# 1LED_pullup.net
KiCad netlist of a schematic drawn in EAGLE
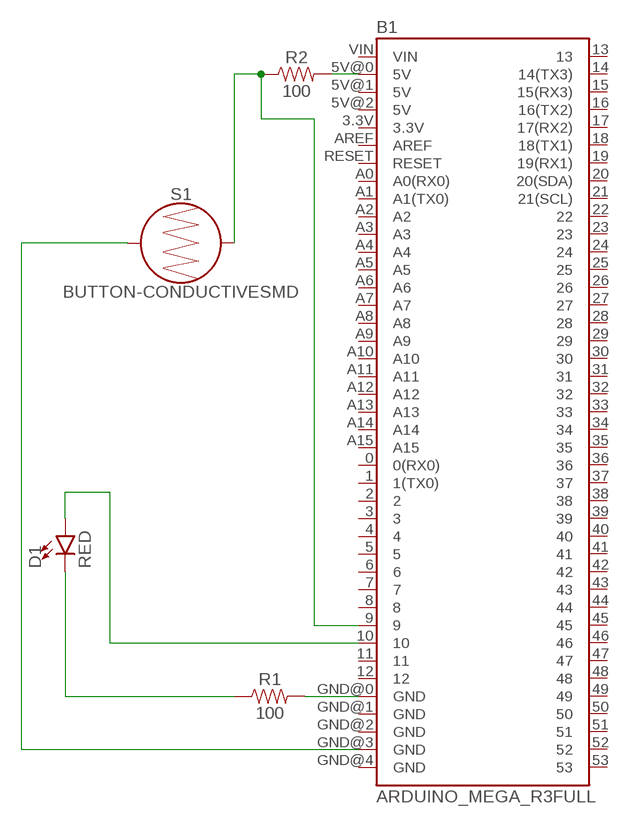
[diagram p0: schematic, sheet 1]

(export (version "E")
  (design (tool "Eeschema 10.0.6"))
  (components
    (comp (ref "B1")
      (value "ARDUINO_MEGA_R3FULL")
      (footprint "eagle-import:ARDUINO_MEGA")
      (libsource (lib "eagle-import") (part "ARDUINO_MEGA_R3FULL"))
    )
    (comp (ref "D1")
      (value "RED")
      (footprint "eagle-import:LED-0603")
      (libsource (lib "eagle-import") (part "LED-RED0603"))
    )
    (comp (ref "R1")
      (value "100")
      (footprint "eagle-import:0603")
      (libsource (lib "eagle-import") (part "100OHM-0603-1/4W-5%"))
    )
    (comp (ref "R2")
      (value "100")
      (footprint "eagle-import:0603")
      (libsource (lib "eagle-import") (part "100OHM-0603-1/4W-5%"))
    )
    (comp (ref "S1")
      (value "BUTTON-CONDUCTIVESMD")
      (footprint "eagle-import:BUTTON-CONDUCTIVE")
      (libsource (lib "eagle-import") (part "BUTTON-CONDUCTIVESMD"))
    )
  )
  (nets
    (net (code "1") (name "Net-(B1-5V-Pad5V@0)") (class "Default")
      (node (ref "B1") (pin "5V@0") (pinfunction "5V_5V@0") (pintype "bidirectional"))
      (node (ref "R2") (pin "2") (pinfunction "2_2") (pintype "passive"))
    )
    (net (code "2") (name "Net-(B1-GND-PadGND@0)") (class "Default")
      (node (ref "B1") (pin "GND@0") (pinfunction "GND_GND@0") (pintype "bidirectional"))
      (node (ref "R1") (pin "2") (pinfunction "2_2") (pintype "passive"))
    )
    (net (code "3") (name "Net-(B1-GND-PadGND@3)") (class "Default")
      (node (ref "B1") (pin "GND@3") (pinfunction "GND_GND@3") (pintype "bidirectional"))
      (node (ref "S1") (pin "1") (pinfunction "1_1") (pintype "passive"))
    )
    (net (code "4") (name "Net-(B1-Pad9)") (class "Default")
      (node (ref "B1") (pin "9") (pinfunction "9_9") (pintype "bidirectional"))
      (node (ref "R2") (pin "1") (pinfunction "1_1") (pintype "passive"))
      (node (ref "S1") (pin "2") (pinfunction "2_2") (pintype "passive"))
    )
    (net (code "5") (name "Net-(B1-Pad10)") (class "Default")
      (node (ref "B1") (pin "10") (pinfunction "10_10") (pintype "bidirectional"))
      (node (ref "D1") (pin "A") (pinfunction "A_A") (pintype "passive"))
    )
    (net (code "6") (name "Net-(D1-PadC)") (class "Default")
      (node (ref "D1") (pin "C") (pinfunction "C_C") (pintype "passive"))
      (node (ref "R1") (pin "1") (pinfunction "1_1") (pintype "passive"))
    )
    (net (code "7") (name "unconnected-(B1-0(RX0)-Pad0)") (class "Default")
      (node (ref "B1") (pin "0") (pinfunction "0(RX0)_0") (pintype "bidirectional"))
    )
    (net (code "8") (name "unconnected-(B1-1(TX0)-Pad1)") (class "Default")
      (node (ref "B1") (pin "1") (pinfunction "1(TX0)_1") (pintype "bidirectional"))
    )
    (net (code "9") (name "unconnected-(B1-5V-Pad5V@1)") (class "Default")
      (node (ref "B1") (pin "5V@1") (pinfunction "5V_5V@1") (pintype "bidirectional"))
    )
    (net (code "10") (name "unconnected-(B1-5V-Pad5V@2)") (class "Default")
      (node (ref "B1") (pin "5V@2") (pinfunction "5V_5V@2") (pintype "bidirectional"))
    )
    (net (code "11") (name "unconnected-(B1-14(TX3)-Pad14)") (class "Default")
      (node (ref "B1") (pin "14") (pinfunction "14(TX3)_14") (pintype "bidirectional"))
    )
    (net (code "12") (name "unconnected-(B1-15(RX3)-Pad15)") (class "Default")
      (node (ref "B1") (pin "15") (pinfunction "15(RX3)_15") (pintype "bidirectional"))
    )
    (net (code "13") (name "unconnected-(B1-16(TX2)-Pad16)") (class "Default")
      (node (ref "B1") (pin "16") (pinfunction "16(TX2)_16") (pintype "bidirectional"))
    )
    (net (code "14") (name "unconnected-(B1-17(RX2)-Pad17)") (class "Default")
      (node (ref "B1") (pin "17") (pinfunction "17(RX2)_17") (pintype "bidirectional"))
    )
    (net (code "15") (name "unconnected-(B1-18(TX1)-Pad18)") (class "Default")
      (node (ref "B1") (pin "18") (pinfunction "18(TX1)_18") (pintype "bidirectional"))
    )
    (net (code "16") (name "unconnected-(B1-19(RX1)-Pad19)") (class "Default")
      (node (ref "B1") (pin "19") (pinfunction "19(RX1)_19") (pintype "bidirectional"))
    )
    (net (code "17") (name "unconnected-(B1-20(SDA)-Pad20)") (class "Default")
      (node (ref "B1") (pin "20") (pinfunction "20(SDA)_20") (pintype "bidirectional"))
    )
    (net (code "18") (name "unconnected-(B1-21(SCL)-Pad21)") (class "Default")
      (node (ref "B1") (pin "21") (pinfunction "21(SCL)_21") (pintype "bidirectional"))
    )
    (net (code "19") (name "unconnected-(B1-A0(RX0)-PadA0)") (class "Default")
      (node (ref "B1") (pin "A0") (pinfunction "A0(RX0)_A0") (pintype "bidirectional"))
    )
    (net (code "20") (name "unconnected-(B1-A1(TX0)-PadA1)") (class "Default")
      (node (ref "B1") (pin "A1") (pinfunction "A1(TX0)_A1") (pintype "bidirectional"))
    )
    (net (code "21") (name "unconnected-(B1-GND-PadGND@1)") (class "Default")
      (node (ref "B1") (pin "GND@1") (pinfunction "GND_GND@1") (pintype "bidirectional"))
    )
    (net (code "22") (name "unconnected-(B1-GND-PadGND@2)") (class "Default")
      (node (ref "B1") (pin "GND@2") (pinfunction "GND_GND@2") (pintype "bidirectional"))
    )
    (net (code "23") (name "unconnected-(B1-GND-PadGND@4)") (class "Default")
      (node (ref "B1") (pin "GND@4") (pinfunction "GND_GND@4") (pintype "bidirectional"))
    )
    (net (code "24") (name "unconnected-(B1-Pad2)") (class "Default")
      (node (ref "B1") (pin "2") (pinfunction "2_2") (pintype "bidirectional"))
    )
    (net (code "25") (name "unconnected-(B1-Pad3)") (class "Default")
      (node (ref "B1") (pin "3") (pinfunction "3_3") (pintype "bidirectional"))
    )
    (net (code "26") (name "unconnected-(B1-Pad3.3V)") (class "Default")
      (node (ref "B1") (pin "3.3V") (pinfunction "3.3V_3.3V") (pintype "bidirectional"))
    )
    (net (code "27") (name "unconnected-(B1-Pad4)") (class "Default")
      (node (ref "B1") (pin "4") (pinfunction "4_4") (pintype "bidirectional"))
    )
    (net (code "28") (name "unconnected-(B1-Pad5)") (class "Default")
      (node (ref "B1") (pin "5") (pinfunction "5_5") (pintype "bidirectional"))
    )
    (net (code "29") (name "unconnected-(B1-Pad6)") (class "Default")
      (node (ref "B1") (pin "6") (pinfunction "6_6") (pintype "bidirectional"))
    )
    (net (code "30") (name "unconnected-(B1-Pad7)") (class "Default")
      (node (ref "B1") (pin "7") (pinfunction "7_7") (pintype "bidirectional"))
    )
    (net (code "31") (name "unconnected-(B1-Pad8)") (class "Default")
      (node (ref "B1") (pin "8") (pinfunction "8_8") (pintype "bidirectional"))
    )
    (net (code "32") (name "unconnected-(B1-Pad11)") (class "Default")
      (node (ref "B1") (pin "11") (pinfunction "11_11") (pintype "bidirectional"))
    )
    (net (code "33") (name "unconnected-(B1-Pad12)") (class "Default")
      (node (ref "B1") (pin "12") (pinfunction "12_12") (pintype "bidirectional"))
    )
    (net (code "34") (name "unconnected-(B1-Pad13)") (class "Default")
      (node (ref "B1") (pin "13") (pinfunction "13_13") (pintype "bidirectional"))
    )
    (net (code "35") (name "unconnected-(B1-Pad22)") (class "Default")
      (node (ref "B1") (pin "22") (pinfunction "22_22") (pintype "bidirectional"))
    )
    (net (code "36") (name "unconnected-(B1-Pad23)") (class "Default")
      (node (ref "B1") (pin "23") (pinfunction "23_23") (pintype "bidirectional"))
    )
    (net (code "37") (name "unconnected-(B1-Pad24)") (class "Default")
      (node (ref "B1") (pin "24") (pinfunction "24_24") (pintype "bidirectional"))
    )
    (net (code "38") (name "unconnected-(B1-Pad25)") (class "Default")
      (node (ref "B1") (pin "25") (pinfunction "25_25") (pintype "bidirectional"))
    )
    (net (code "39") (name "unconnected-(B1-Pad26)") (class "Default")
      (node (ref "B1") (pin "26") (pinfunction "26_26") (pintype "bidirectional"))
    )
    (net (code "40") (name "unconnected-(B1-Pad27)") (class "Default")
      (node (ref "B1") (pin "27") (pinfunction "27_27") (pintype "bidirectional"))
    )
    (net (code "41") (name "unconnected-(B1-Pad28)") (class "Default")
      (node (ref "B1") (pin "28") (pinfunction "28_28") (pintype "bidirectional"))
    )
    (net (code "42") (name "unconnected-(B1-Pad29)") (class "Default")
      (node (ref "B1") (pin "29") (pinfunction "29_29") (pintype "bidirectional"))
    )
    (net (code "43") (name "unconnected-(B1-Pad30)") (class "Default")
      (node (ref "B1") (pin "30") (pinfunction "30_30") (pintype "bidirectional"))
    )
    (net (code "44") (name "unconnected-(B1-Pad31)") (class "Default")
      (node (ref "B1") (pin "31") (pinfunction "31_31") (pintype "bidirectional"))
    )
    (net (code "45") (name "unconnected-(B1-Pad32)") (class "Default")
      (node (ref "B1") (pin "32") (pinfunction "32_32") (pintype "bidirectional"))
    )
    (net (code "46") (name "unconnected-(B1-Pad33)") (class "Default")
      (node (ref "B1") (pin "33") (pinfunction "33_33") (pintype "bidirectional"))
    )
    (net (code "47") (name "unconnected-(B1-Pad34)") (class "Default")
      (node (ref "B1") (pin "34") (pinfunction "34_34") (pintype "bidirectional"))
    )
    (net (code "48") (name "unconnected-(B1-Pad35)") (class "Default")
      (node (ref "B1") (pin "35") (pinfunction "35_35") (pintype "bidirectional"))
    )
    (net (code "49") (name "unconnected-(B1-Pad36)") (class "Default")
      (node (ref "B1") (pin "36") (pinfunction "36_36") (pintype "bidirectional"))
    )
    (net (code "50") (name "unconnected-(B1-Pad37)") (class "Default")
      (node (ref "B1") (pin "37") (pinfunction "37_37") (pintype "bidirectional"))
    )
    (net (code "51") (name "unconnected-(B1-Pad38)") (class "Default")
      (node (ref "B1") (pin "38") (pinfunction "38_38") (pintype "bidirectional"))
    )
    (net (code "52") (name "unconnected-(B1-Pad39)") (class "Default")
      (node (ref "B1") (pin "39") (pinfunction "39_39") (pintype "bidirectional"))
    )
    (net (code "53") (name "unconnected-(B1-Pad40)") (class "Default")
      (node (ref "B1") (pin "40") (pinfunction "40_40") (pintype "bidirectional"))
    )
    (net (code "54") (name "unconnected-(B1-Pad41)") (class "Default")
      (node (ref "B1") (pin "41") (pinfunction "41_41") (pintype "bidirectional"))
    )
    (net (code "55") (name "unconnected-(B1-Pad42)") (class "Default")
      (node (ref "B1") (pin "42") (pinfunction "42_42") (pintype "bidirectional"))
    )
    (net (code "56") (name "unconnected-(B1-Pad43)") (class "Default")
      (node (ref "B1") (pin "43") (pinfunction "43_43") (pintype "bidirectional"))
    )
    (net (code "57") (name "unconnected-(B1-Pad44)") (class "Default")
      (node (ref "B1") (pin "44") (pinfunction "44_44") (pintype "bidirectional"))
    )
    (net (code "58") (name "unconnected-(B1-Pad45)") (class "Default")
      (node (ref "B1") (pin "45") (pinfunction "45_45") (pintype "bidirectional"))
    )
    (net (code "59") (name "unconnected-(B1-Pad46)") (class "Default")
      (node (ref "B1") (pin "46") (pinfunction "46_46") (pintype "bidirectional"))
    )
    (net (code "60") (name "unconnected-(B1-Pad47)") (class "Default")
      (node (ref "B1") (pin "47") (pinfunction "47_47") (pintype "bidirectional"))
    )
    (net (code "61") (name "unconnected-(B1-Pad48)") (class "Default")
      (node (ref "B1") (pin "48") (pinfunction "48_48") (pintype "bidirectional"))
    )
    (net (code "62") (name "unconnected-(B1-Pad49)") (class "Default")
      (node (ref "B1") (pin "49") (pinfunction "49_49") (pintype "bidirectional"))
    )
    (net (code "63") (name "unconnected-(B1-Pad50)") (class "Default")
      (node (ref "B1") (pin "50") (pinfunction "50_50") (pintype "bidirectional"))
    )
    (net (code "64") (name "unconnected-(B1-Pad51)") (class "Default")
      (node (ref "B1") (pin "51") (pinfunction "51_51") (pintype "bidirectional"))
    )
    (net (code "65") (name "unconnected-(B1-Pad52)") (class "Default")
      (node (ref "B1") (pin "52") (pinfunction "52_52") (pintype "bidirectional"))
    )
    (net (code "66") (name "unconnected-(B1-Pad53)") (class "Default")
      (node (ref "B1") (pin "53") (pinfunction "53_53") (pintype "bidirectional"))
    )
    (net (code "67") (name "unconnected-(B1-PadA2)") (class "Default")
      (node (ref "B1") (pin "A2") (pinfunction "A2_A2") (pintype "bidirectional"))
    )
    (net (code "68") (name "unconnected-(B1-PadA3)") (class "Default")
      (node (ref "B1") (pin "A3") (pinfunction "A3_A3") (pintype "bidirectional"))
    )
    (net (code "69") (name "unconnected-(B1-PadA4)") (class "Default")
      (node (ref "B1") (pin "A4") (pinfunction "A4_A4") (pintype "bidirectional"))
    )
    (net (code "70") (name "unconnected-(B1-PadA5)") (class "Default")
      (node (ref "B1") (pin "A5") (pinfunction "A5_A5") (pintype "bidirectional"))
    )
    (net (code "71") (name "unconnected-(B1-PadA6)") (class "Default")
      (node (ref "B1") (pin "A6") (pinfunction "A6_A6") (pintype "bidirectional"))
    )
    (net (code "72") (name "unconnected-(B1-PadA7)") (class "Default")
      (node (ref "B1") (pin "A7") (pinfunction "A7_A7") (pintype "bidirectional"))
    )
    (net (code "73") (name "unconnected-(B1-PadA8)") (class "Default")
      (node (ref "B1") (pin "A8") (pinfunction "A8_A8") (pintype "bidirectional"))
    )
    (net (code "74") (name "unconnected-(B1-PadA9)") (class "Default")
      (node (ref "B1") (pin "A9") (pinfunction "A9_A9") (pintype "bidirectional"))
    )
    (net (code "75") (name "unconnected-(B1-PadA10)") (class "Default")
      (node (ref "B1") (pin "A10") (pinfunction "A10_A10") (pintype "bidirectional"))
    )
    (net (code "76") (name "unconnected-(B1-PadA11)") (class "Default")
      (node (ref "B1") (pin "A11") (pinfunction "A11_A11") (pintype "bidirectional"))
    )
    (net (code "77") (name "unconnected-(B1-PadA12)") (class "Default")
      (node (ref "B1") (pin "A12") (pinfunction "A12_A12") (pintype "bidirectional"))
    )
    (net (code "78") (name "unconnected-(B1-PadA13)") (class "Default")
      (node (ref "B1") (pin "A13") (pinfunction "A13_A13") (pintype "bidirectional"))
    )
    (net (code "79") (name "unconnected-(B1-PadA14)") (class "Default")
      (node (ref "B1") (pin "A14") (pinfunction "A14_A14") (pintype "bidirectional"))
    )
    (net (code "80") (name "unconnected-(B1-PadA15)") (class "Default")
      (node (ref "B1") (pin "A15") (pinfunction "A15_A15") (pintype "bidirectional"))
    )
    (net (code "81") (name "unconnected-(B1-PadAREF)") (class "Default")
      (node (ref "B1") (pin "AREF") (pinfunction "AREF_AREF") (pintype "bidirectional"))
    )
    (net (code "82") (name "unconnected-(B1-PadRESET)") (class "Default")
      (node (ref "B1") (pin "RESET") (pinfunction "RESET_RESET") (pintype "bidirectional"))
    )
    (net (code "83") (name "unconnected-(B1-PadVIN)") (class "Default")
      (node (ref "B1") (pin "VIN") (pinfunction "VIN_VIN") (pintype "bidirectional"))
    )
  )
)
